# Movimiento.net
KiCad netlist of a schematic drawn in EAGLE
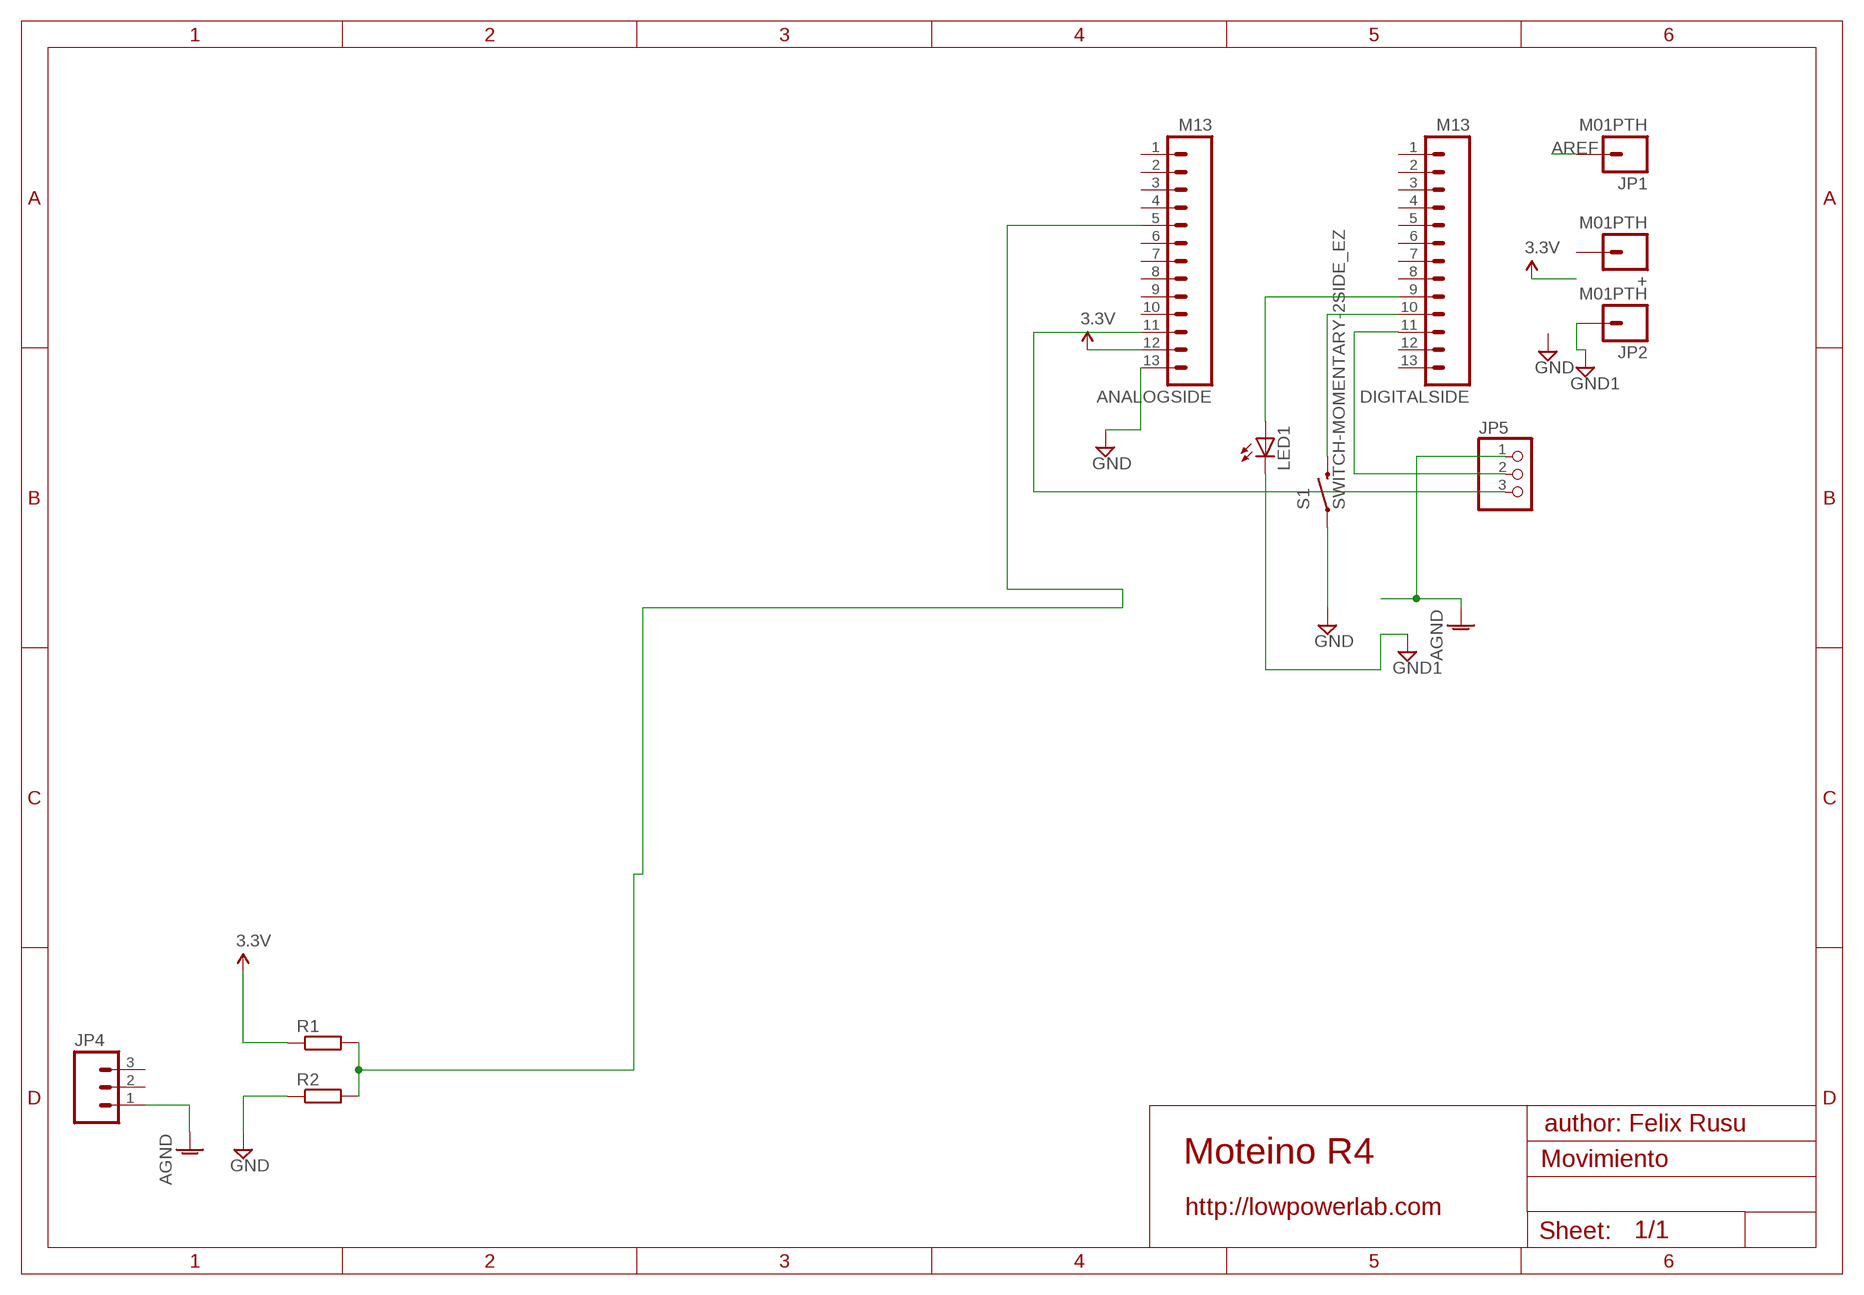
[diagram p0: schematic, sheet 1]

(export (version "E")
  (design (tool "Eeschema 10.0.6"))
  (components
    (comp (ref "+")
      (value "M01PTH")
      (footprint "eagle-import:1X01")
      (libsource (lib "eagle-import") (part "M01PTH"))
    )
    (comp (ref "ANALOGSIDE")
      (value "M13")
      (footprint "eagle-import:1X13")
      (libsource (lib "eagle-import") (part "M13"))
    )
    (comp (ref "DIGITALSIDE")
      (value "M13")
      (footprint "eagle-import:1X13")
      (libsource (lib "eagle-import") (part "M13"))
    )
    (comp (ref "JP1")
      (value "M01PTH")
      (footprint "eagle-import:1X01")
      (libsource (lib "eagle-import") (part "M01PTH"))
    )
    (comp (ref "JP2")
      (value "M01PTH")
      (footprint "eagle-import:1X01")
      (libsource (lib "eagle-import") (part "M01PTH"))
    )
    (comp (ref "JP4")
      (value "M03PTH")
      (footprint "eagle-import:1X03")
      (libsource (lib "eagle-import") (part "M03PTH"))
    )
    (comp (ref "JP5")
      (value "PINHD-1X3")
      (footprint "eagle-import:1X03")
      (libsource (lib "eagle-import") (part "PINHD-1X3"))
    )
    (comp (ref "LED1")
      (value "LED3MM")
      (footprint "eagle-import:LED3MM")
      (libsource (lib "eagle-import") (part "LED3MM"))
    )
    (comp (ref "R1")
      (value "R-EU_0204/7")
      (footprint "eagle-import:0204_7")
      (libsource (lib "eagle-import") (part "R-EU_0204/7"))
    )
    (comp (ref "R2")
      (value "R-EU_0204/7")
      (footprint "eagle-import:0204_7")
      (libsource (lib "eagle-import") (part "R-EU_0204/7"))
    )
    (comp (ref "S1")
      (value "SWITCH-MOMENTARY-2SIDE_EZ")
      (footprint "eagle-import:TACTILE-PTH-SIDEEZ")
      (libsource (lib "eagle-import") (part "SWITCH-MOMENTARY-2SIDE_EZ"))
    )
  )
  (nets
    (net (code "1") (name "/AREF") (class "Default")
      (node (ref "JP1") (pin "1") (pinfunction "1_1") (pintype "passive"))
    )
    (net (code "2") (name "3.3V") (class "Default")
      (node (ref "ANALOGSIDE") (pin "12") (pinfunction "12_12") (pintype "passive"))
      (node (ref "R1") (pin "1") (pinfunction "1_1") (pintype "passive"))
    )
    (net (code "3") (name "AGND") (class "Default")
      (node (ref "JP4") (pin "1") (pinfunction "1_1") (pintype "passive"))
      (node (ref "JP5") (pin "1") (pinfunction "1_1") (pintype "passive"))
    )
    (net (code "4") (name "GND") (class "Default")
      (node (ref "ANALOGSIDE") (pin "13") (pinfunction "13_13") (pintype "passive"))
      (node (ref "R2") (pin "1") (pinfunction "1_1") (pintype "passive"))
      (node (ref "S1") (pin "1") (pinfunction "1_1") (pintype "passive"))
    )
    (net (code "5") (name "GND1") (class "Default")
      (node (ref "JP2") (pin "1") (pinfunction "1_1") (pintype "passive"))
      (node (ref "LED1") (pin "K") (pinfunction "C_K") (pintype "passive"))
    )
    (net (code "6") (name "Net-(ANALOGSIDE-Pad5)") (class "Default")
      (node (ref "ANALOGSIDE") (pin "5") (pinfunction "5_5") (pintype "passive"))
      (node (ref "R1") (pin "2") (pinfunction "2_2") (pintype "passive"))
      (node (ref "R2") (pin "2") (pinfunction "2_2") (pintype "passive"))
    )
    (net (code "7") (name "Net-(ANALOGSIDE-Pad11)") (class "Default")
      (node (ref "ANALOGSIDE") (pin "11") (pinfunction "11_11") (pintype "passive"))
      (node (ref "JP5") (pin "3") (pinfunction "3_3") (pintype "passive"))
    )
    (net (code "8") (name "Net-(DIGITALSIDE-Pad9)") (class "Default")
      (node (ref "DIGITALSIDE") (pin "9") (pinfunction "9_9") (pintype "passive"))
      (node (ref "LED1") (pin "A") (pinfunction "A_A") (pintype "passive"))
    )
    (net (code "9") (name "Net-(DIGITALSIDE-Pad10)") (class "Default")
      (node (ref "DIGITALSIDE") (pin "10") (pinfunction "10_10") (pintype "passive"))
      (node (ref "S1") (pin "2") (pinfunction "2_2") (pintype "passive"))
    )
    (net (code "10") (name "Net-(DIGITALSIDE-Pad11)") (class "Default")
      (node (ref "DIGITALSIDE") (pin "11") (pinfunction "11_11") (pintype "passive"))
      (node (ref "JP5") (pin "2") (pinfunction "2_2") (pintype "passive"))
    )
    (net (code "11") (name "unconnected-(+-Pad1)") (class "Default")
      (node (ref "+") (pin "1") (pinfunction "1_1") (pintype "passive"))
    )
    (net (code "12") (name "unconnected-(ANALOGSIDE-Pad1)") (class "Default")
      (node (ref "ANALOGSIDE") (pin "1") (pinfunction "1_1") (pintype "passive"))
    )
    (net (code "13") (name "unconnected-(ANALOGSIDE-Pad2)") (class "Default")
      (node (ref "ANALOGSIDE") (pin "2") (pinfunction "2_2") (pintype "passive"))
    )
    (net (code "14") (name "unconnected-(ANALOGSIDE-Pad3)") (class "Default")
      (node (ref "ANALOGSIDE") (pin "3") (pinfunction "3_3") (pintype "passive"))
    )
    (net (code "15") (name "unconnected-(ANALOGSIDE-Pad4)") (class "Default")
      (node (ref "ANALOGSIDE") (pin "4") (pinfunction "4_4") (pintype "passive"))
    )
    (net (code "16") (name "unconnected-(ANALOGSIDE-Pad6)") (class "Default")
      (node (ref "ANALOGSIDE") (pin "6") (pinfunction "6_6") (pintype "passive"))
    )
    (net (code "17") (name "unconnected-(ANALOGSIDE-Pad7)") (class "Default")
      (node (ref "ANALOGSIDE") (pin "7") (pinfunction "7_7") (pintype "passive"))
    )
    (net (code "18") (name "unconnected-(ANALOGSIDE-Pad8)") (class "Default")
      (node (ref "ANALOGSIDE") (pin "8") (pinfunction "8_8") (pintype "passive"))
    )
    (net (code "19") (name "unconnected-(ANALOGSIDE-Pad9)") (class "Default")
      (node (ref "ANALOGSIDE") (pin "9") (pinfunction "9_9") (pintype "passive"))
    )
    (net (code "20") (name "unconnected-(ANALOGSIDE-Pad10)") (class "Default")
      (node (ref "ANALOGSIDE") (pin "10") (pinfunction "10_10") (pintype "passive"))
    )
    (net (code "21") (name "unconnected-(DIGITALSIDE-Pad1)") (class "Default")
      (node (ref "DIGITALSIDE") (pin "1") (pinfunction "1_1") (pintype "passive"))
    )
    (net (code "22") (name "unconnected-(DIGITALSIDE-Pad2)") (class "Default")
      (node (ref "DIGITALSIDE") (pin "2") (pinfunction "2_2") (pintype "passive"))
    )
    (net (code "23") (name "unconnected-(DIGITALSIDE-Pad3)") (class "Default")
      (node (ref "DIGITALSIDE") (pin "3") (pinfunction "3_3") (pintype "passive"))
    )
    (net (code "24") (name "unconnected-(DIGITALSIDE-Pad4)") (class "Default")
      (node (ref "DIGITALSIDE") (pin "4") (pinfunction "4_4") (pintype "passive"))
    )
    (net (code "25") (name "unconnected-(DIGITALSIDE-Pad5)") (class "Default")
      (node (ref "DIGITALSIDE") (pin "5") (pinfunction "5_5") (pintype "passive"))
    )
    (net (code "26") (name "unconnected-(DIGITALSIDE-Pad6)") (class "Default")
      (node (ref "DIGITALSIDE") (pin "6") (pinfunction "6_6") (pintype "passive"))
    )
    (net (code "27") (name "unconnected-(DIGITALSIDE-Pad7)") (class "Default")
      (node (ref "DIGITALSIDE") (pin "7") (pinfunction "7_7") (pintype "passive"))
    )
    (net (code "28") (name "unconnected-(DIGITALSIDE-Pad8)") (class "Default")
      (node (ref "DIGITALSIDE") (pin "8") (pinfunction "8_8") (pintype "passive"))
    )
    (net (code "29") (name "unconnected-(DIGITALSIDE-Pad12)") (class "Default")
      (node (ref "DIGITALSIDE") (pin "12") (pinfunction "12_12") (pintype "passive"))
    )
    (net (code "30") (name "unconnected-(DIGITALSIDE-Pad13)") (class "Default")
      (node (ref "DIGITALSIDE") (pin "13") (pinfunction "13_13") (pintype "passive"))
    )
    (net (code "31") (name "unconnected-(JP4-Pad2)") (class "Default")
      (node (ref "JP4") (pin "2") (pinfunction "2_2") (pintype "passive"))
    )
    (net (code "32") (name "unconnected-(JP4-Pad3)") (class "Default")
      (node (ref "JP4") (pin "3") (pinfunction "3_3") (pintype "passive"))
    )
  )
)
